# Sheet3.net
KiCad netlist of a schematic drawn in Altium Designer
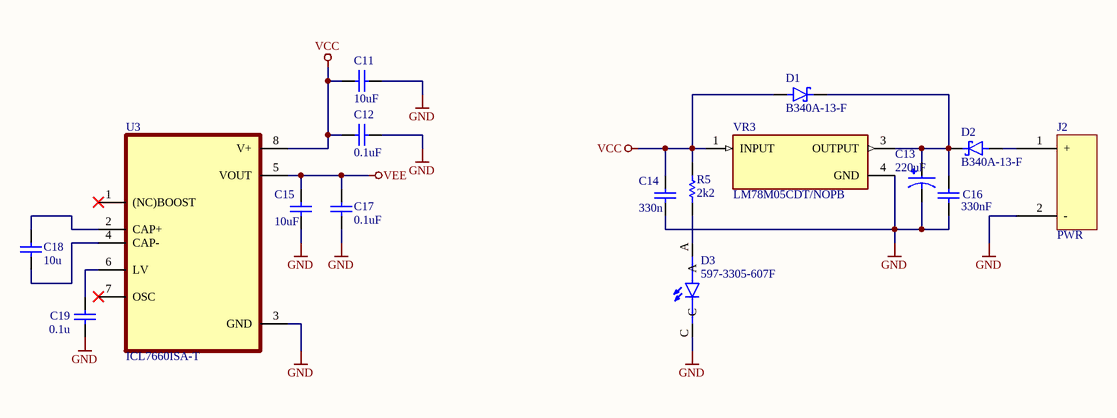
[diagram p0: Sheet3.SchDoc]

(export (version "E")
  (design (tool "Eeschema 10.0.6"))
  (components
    (comp (ref "C11")
      (value "10uF")
      (footprint "CAPC2012X150N")
      (description "Capacitor")
      (libsource (lib "Simulation Generic Components") (part "Capacitor"))
    )
    (comp (ref "C12")
      (value "0.1uF")
      (footprint "CAPC2012X150N")
      (description "Capacitor")
      (libsource (lib "Simulation Generic Components") (part "Capacitor"))
    )
    (comp (ref "C13")
      (value "220uF")
      (footprint "CAP_EEEFT1V331AP")
      (fields (field (name "MF") "Panasonic Electronic") (field (name "MP") "EEE-FT1V331AP"))
      (libsource (lib "EEEFT1V331AP") (part "EEEFT1V331AP"))
    )
    (comp (ref "C14")
      (value "330n")
      (footprint "CAPC2012X150N")
      (description "Capacitor")
      (libsource (lib "Simulation Generic Components") (part "Capacitor"))
    )
    (comp (ref "C15")
      (value "10uF")
      (footprint "CAPC2012X150N")
      (description "Capacitor")
      (libsource (lib "Simulation Generic Components") (part "Capacitor"))
    )
    (comp (ref "C16")
      (value "330nF")
      (footprint "CAPC2012X150N")
      (description "Capacitor")
      (libsource (lib "Simulation Generic Components") (part "Capacitor"))
    )
    (comp (ref "C17")
      (value "0.1uF")
      (footprint "CAPC2012X150N")
      (description "Capacitor")
      (libsource (lib "Simulation Generic Components") (part "Capacitor"))
    )
    (comp (ref "C18")
      (value "10u")
      (footprint "CAPC2012X150N")
      (description "Capacitor")
      (libsource (lib "Simulation Generic Components") (part "Capacitor"))
    )
    (comp (ref "C19")
      (value "0.1u")
      (footprint "CAPC2012X150N")
      (description "Capacitor")
      (libsource (lib "Simulation Generic Components") (part "Capacitor"))
    )
    (comp (ref "D1")
      (value "B340A-13-F")
      (footprint "DIOM5226X240N")
      (description "Schottky Diode 3A 40V 0.5Vf SMA ¦ Diodes Inc B340A-13-F")
      (fields (field (name "MF") "Diodes Inc."))
      (libsource (lib "B340A-13-F") (part "B340A-13-F"))
    )
    (comp (ref "D2")
      (value "B340A-13-F")
      (footprint "DIOM5226X240N")
      (description "Schottky Diode 3A 40V 0.5Vf SMA ¦ Diodes Inc B340A-13-F")
      (fields (field (name "MF") "Diodes Inc."))
      (libsource (lib "B340A-13-F") (part "B340A-13-F"))
    )
    (comp (ref "D3")
      (value "597-3305-607F")
      (footprint "LEDC2012X70N")
      (description "LED Uni-Color Green 4-Pin Chip 0805 T/R")
      (libsource (lib "597-3305-607F") (part "597-3305-607F"))
    )
    (comp (ref "J2")
      (value "PWR")
      (footprint "JST_B2B-XH-A_(LF)(SN)")
      (libsource (lib "Schlib1") (part "Outp"))
    )
    (comp (ref "R5")
      (value "2k2")
      (footprint "RES_ERA6AHD330V")
      (description "Resistor")
      (libsource (lib "Simulation Generic Components") (part "Resistor"))
    )
    (comp (ref "U3")
      (value "ICL7660ISA-T")
      (footprint "SOIC127P600X175-8N")
      (description "Switched-Capacitor Voltage Converters")
      (fields (field (name "MF") "Analog Devices") (field (name "MP") "ICL7660ISA+"))
      (libsource (lib "ICL7660ISA-T") (part "ICL7660ISA-T"))
    )
    (comp (ref "VR3")
      (value "LM78M05CDT/NOPB")
      (footprint "TO228P991X255-3N")
      (description "500-mA, 35-V, linear voltage regulator for 5 V")
      (fields (field (name "MF") "Texas Instruments"))
      (libsource (lib "LM78M05CDT_NOPB") (part "LM78M05CDT/NOPB"))
    )
  )
  (nets
    (net (code "1") (name "GND") (class "Default")
      (node (ref "C11") (pin "2") (pinfunction "2_2") (pintype "passive"))
      (node (ref "C12") (pin "1") (pinfunction "1_1") (pintype "passive"))
      (node (ref "C13") (pin "2") (pinfunction "2_2") (pintype "passive"))
      (node (ref "C14") (pin "2") (pinfunction "2_2") (pintype "passive"))
      (node (ref "C15") (pin "1") (pinfunction "1_1") (pintype "passive"))
      (node (ref "C16") (pin "2") (pinfunction "2_2") (pintype "passive"))
      (node (ref "C17") (pin "1") (pinfunction "1_1") (pintype "passive"))
      (node (ref "C19") (pin "1") (pinfunction "1_1") (pintype "passive"))
      (node (ref "D3") (pin "C") (pinfunction "C_C") (pintype "passive"))
      (node (ref "J2") (pin "2") (pinfunction "-_2") (pintype "passive"))
      (node (ref "U3") (pin "3") (pinfunction "GND_3") (pintype "power_in"))
      (node (ref "VR3") (pin "4") (pinfunction "GND_4") (pintype "power_in"))
    )
    (net (code "2") (name "Net-(D3-PadA)") (class "Default")
      (node (ref "D3") (pin "A") (pinfunction "A_A") (pintype "passive"))
      (node (ref "R5") (pin "1") (pinfunction "1_1") (pintype "passive"))
    )
    (net (code "3") (name "Net-(J2-+)") (class "Default")
      (node (ref "D2") (pin "A") (pinfunction "A_A") (pintype "passive"))
      (node (ref "J2") (pin "1") (pinfunction "+_1") (pintype "passive"))
    )
    (net (code "4") (name "Net-(U3-CAP+)") (class "Default")
      (node (ref "C18") (pin "2") (pinfunction "2_2") (pintype "passive"))
      (node (ref "U3") (pin "2") (pinfunction "CAP+_2") (pintype "passive"))
    )
    (net (code "5") (name "Net-(U3-CAP-)") (class "Default")
      (node (ref "C18") (pin "1") (pinfunction "1_1") (pintype "passive"))
      (node (ref "U3") (pin "4") (pinfunction "CAP-_4") (pintype "passive"))
    )
    (net (code "6") (name "Net-(U3-LV)") (class "Default")
      (node (ref "C19") (pin "2") (pinfunction "2_2") (pintype "passive"))
      (node (ref "U3") (pin "6") (pinfunction "LV_6") (pintype "passive"))
    )
    (net (code "7") (name "Net-(VR3-OUTPUT)") (class "Default")
      (node (ref "C13") (pin "1") (pinfunction "1_1") (pintype "passive"))
      (node (ref "C16") (pin "1") (pinfunction "1_1") (pintype "passive"))
      (node (ref "D1") (pin "C") (pinfunction "C_C") (pintype "passive"))
      (node (ref "D2") (pin "C") (pinfunction "C_C") (pintype "passive"))
      (node (ref "VR3") (pin "3") (pinfunction "OUTPUT_3") (pintype "output"))
    )
    (net (code "8") (name "VCC") (class "Default")
      (node (ref "C11") (pin "1") (pinfunction "1_1") (pintype "passive"))
      (node (ref "C12") (pin "2") (pinfunction "2_2") (pintype "passive"))
      (node (ref "C14") (pin "1") (pinfunction "1_1") (pintype "passive"))
      (node (ref "D1") (pin "A") (pinfunction "A_A") (pintype "passive"))
      (node (ref "R5") (pin "2") (pinfunction "2_2") (pintype "passive"))
      (node (ref "U3") (pin "8") (pinfunction "V+_8") (pintype "power_in"))
      (node (ref "VR3") (pin "1") (pinfunction "INPUT_1") (pintype "input"))
    )
    (net (code "9") (name "VEE") (class "Default")
      (node (ref "C15") (pin "2") (pinfunction "2_2") (pintype "passive"))
      (node (ref "C17") (pin "2") (pinfunction "2_2") (pintype "passive"))
      (node (ref "U3") (pin "5") (pinfunction "VOUT_5") (pintype "passive"))
    )
    (net (code "10") (name "unconnected-(U3-(NC)BOOST-Pad1)") (class "Default")
      (node (ref "U3") (pin "1") (pinfunction "(NC)BOOST_1") (pintype "passive+no_connect"))
    )
    (net (code "11") (name "unconnected-(U3-OSC-Pad7)") (class "Default")
      (node (ref "U3") (pin "7") (pinfunction "OSC_7") (pintype "tri_state+no_connect"))
    )
  )
)
